# Sheet1.net
KiCad netlist of a schematic drawn in Altium Designer
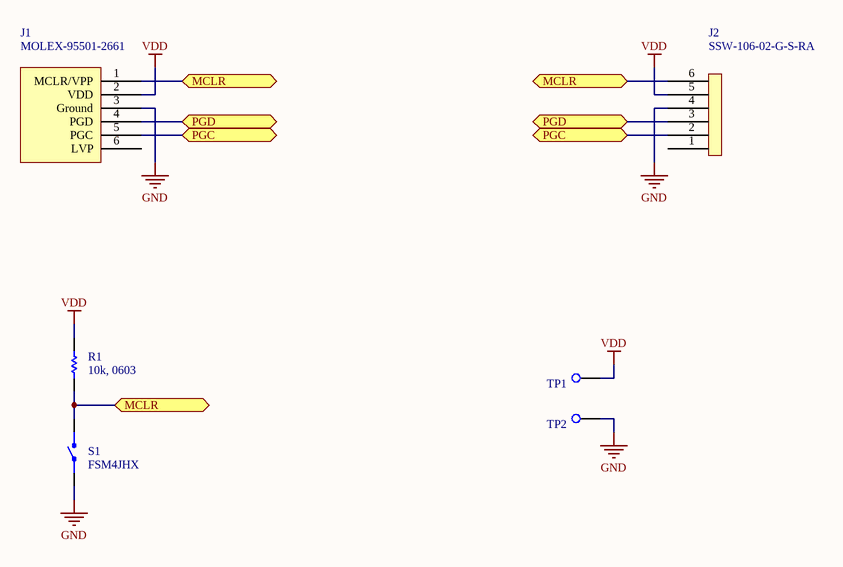
[diagram p0: Sheet1.SchDoc]

(export (version "E")
  (design (tool "Eeschema 10.0.6"))
  (components
    (comp (ref "J1")
      (value "MOLEX-95501-2661")
      (footprint "Molex 95501-2661")
      (libsource (lib "x-io") (part "MPLAB ICSP"))
    )
    (comp (ref "J2")
      (value "SSW-106-02-G-S-RA")
      (footprint "SSW-106-02-G-S-RA")
      (libsource (lib "x-io") (part "SSW-106-02-G-S-RA"))
    )
    (comp (ref "R1")
      (value "10k, 0603")
      (footprint "Resistor 0603")
      (libsource (lib "x-io") (part "Resistor"))
    )
    (comp (ref "S1") (value "FSM4JHX") (footprint "FSM4JHX") (libsource (lib "x-io") (part "Switch")))
    (comp (ref "TP1")
      (value "Test Point")
      (footprint "Keystone 5010")
      (libsource (lib "x-io") (part "Test Point"))
    )
    (comp (ref "TP2")
      (value "Test Point")
      (footprint "Keystone 5011")
      (libsource (lib "x-io") (part "Test Point"))
    )
  )
  (nets
    (net (code "1") (name "/MCLR") (class "Default")
      (node (ref "J1") (pin "1") (pinfunction "MCLR/VPP_1") (pintype "passive"))
      (node (ref "J2") (pin "6") (pinfunction "6_6") (pintype "passive"))
      (node (ref "R1") (pin "1") (pinfunction "1_1") (pintype "passive"))
      (node (ref "S1") (pin "2") (pinfunction "2_2") (pintype "passive"))
    )
    (net (code "2") (name "/PGC") (class "Default")
      (node (ref "J1") (pin "5") (pinfunction "PGC_5") (pintype "passive"))
      (node (ref "J2") (pin "2") (pinfunction "2_2") (pintype "passive"))
    )
    (net (code "3") (name "/PGD") (class "Default")
      (node (ref "J1") (pin "4") (pinfunction "PGD_4") (pintype "passive"))
      (node (ref "J2") (pin "3") (pinfunction "3_3") (pintype "passive"))
    )
    (net (code "4") (name "GND") (class "Default")
      (node (ref "J1") (pin "3") (pinfunction "Ground_3") (pintype "passive"))
      (node (ref "J2") (pin "4") (pinfunction "4_4") (pintype "passive"))
      (node (ref "S1") (pin "1") (pinfunction "1_1") (pintype "passive"))
      (node (ref "TP2") (pin "1") (pinfunction "1_1") (pintype "passive"))
    )
    (net (code "5") (name "VDD") (class "Default")
      (node (ref "J1") (pin "2") (pinfunction "VDD_2") (pintype "passive"))
      (node (ref "J2") (pin "5") (pinfunction "5_5") (pintype "passive"))
      (node (ref "R1") (pin "2") (pinfunction "2_2") (pintype "passive"))
      (node (ref "TP1") (pin "1") (pinfunction "1_1") (pintype "passive"))
    )
    (net (code "6") (name "unconnected-(J1-LVP-Pad6)") (class "Default")
      (node (ref "J1") (pin "6") (pinfunction "LVP_6") (pintype "passive"))
    )
    (net (code "7") (name "unconnected-(J2-Pad1)") (class "Default")
      (node (ref "J2") (pin "1") (pinfunction "1_1") (pintype "passive"))
    )
  )
)
